# FPGA_VCC.net
KiCad netlist of a schematic drawn in Altium Designer
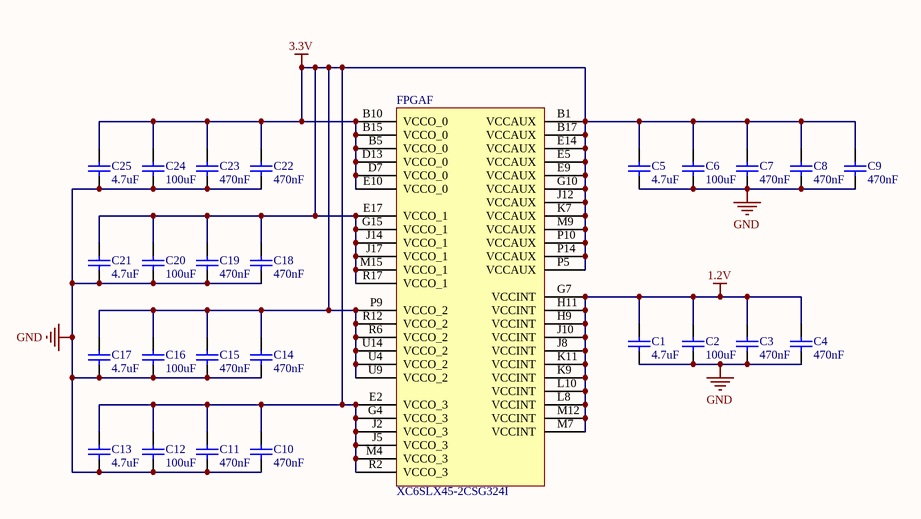
[diagram p0: FPGA_VCC.SchDoc]

(export (version "E")
  (design (tool "Eeschema 10.0.6"))
  (components
    (comp (ref "C1")
      (value "4.7uF")
      (footprint "CAPC0603(1608)100_N")
      (description "CAP 0.5pF 10V Â±0.1pF 0603 (1608 Metric) Thickness 1mm SMD")
      (fields (field (name "TOLERANCE") "Â±0.1pF"))
      (libsource (lib "Altium Inc") (part "CMP-1035-00001-1"))
    )
    (comp (ref "C2")
      (value "100uF")
      (footprint "CAPC0805(2012)75_N")
      (description "CAP 0.5pF 10V Â±0.1pF 0805 (2012 Metric) Thickness 0.75mm SMD")
      (fields (field (name "TOLERANCE") "Â±0.1pF"))
      (libsource (lib "Altium Inc") (part "CMP-1036-00001-1"))
    )
    (comp (ref "C3")
      (value "470nF")
      (footprint "CAPC0603(1608)100_N")
      (description "CAP 0.5pF 10V Â±0.1pF 0603 (1608 Metric) Thickness 1mm SMD")
      (fields (field (name "TOLERANCE") "Â±0.1pF"))
      (libsource (lib "Altium Inc") (part "CMP-1035-00001-1"))
    )
    (comp (ref "C4")
      (value "470nF")
      (footprint "CAPC0603(1608)100_N")
      (description "CAP 0.5pF 10V Â±0.1pF 0603 (1608 Metric) Thickness 1mm SMD")
      (fields (field (name "TOLERANCE") "Â±0.1pF"))
      (libsource (lib "Altium Inc") (part "CMP-1035-00001-1"))
    )
    (comp (ref "C5")
      (value "4.7uF")
      (footprint "CAPC0603(1608)100_N")
      (description "CAP 0.5pF 10V Â±0.1pF 0603 (1608 Metric) Thickness 1mm SMD")
      (fields (field (name "TOLERANCE") "Â±0.1pF"))
      (libsource (lib "Altium Inc") (part "CMP-1035-00001-1"))
    )
    (comp (ref "C6")
      (value "100uF")
      (footprint "CAPC0805(2012)75_N")
      (description "CAP 0.5pF 10V Â±0.1pF 0805 (2012 Metric) Thickness 0.75mm SMD")
      (fields (field (name "TOLERANCE") "Â±0.1pF"))
      (libsource (lib "Altium Inc") (part "CMP-1036-00001-1"))
    )
    (comp (ref "C7")
      (value "470nF")
      (footprint "CAPC0603(1608)100_N")
      (description "CAP 0.5pF 10V Â±0.1pF 0603 (1608 Metric) Thickness 1mm SMD")
      (fields (field (name "TOLERANCE") "Â±0.1pF"))
      (libsource (lib "Altium Inc") (part "CMP-1035-00001-1"))
    )
    (comp (ref "C8")
      (value "470nF")
      (footprint "CAPC0603(1608)100_N")
      (description "CAP 0.5pF 10V Â±0.1pF 0603 (1608 Metric) Thickness 1mm SMD")
      (fields (field (name "TOLERANCE") "Â±0.1pF"))
      (libsource (lib "Altium Inc") (part "CMP-1035-00001-1"))
    )
    (comp (ref "C9")
      (value "470nF")
      (footprint "CAPC0603(1608)100_N")
      (description "CAP 0.5pF 10V Â±0.1pF 0603 (1608 Metric) Thickness 1mm SMD")
      (fields (field (name "TOLERANCE") "Â±0.1pF"))
      (libsource (lib "Altium Inc") (part "CMP-1035-00001-1"))
    )
    (comp (ref "C10")
      (value "470nF")
      (footprint "CAPC0603(1608)100_N")
      (description "CAP 0.5pF 10V Â±0.1pF 0603 (1608 Metric) Thickness 1mm SMD")
      (fields (field (name "TOLERANCE") "Â±0.1pF"))
      (libsource (lib "Altium Inc") (part "CMP-1035-00001-1"))
    )
    (comp (ref "C11")
      (value "470nF")
      (footprint "CAPC0603(1608)100_N")
      (description "CAP 0.5pF 10V Â±0.1pF 0603 (1608 Metric) Thickness 1mm SMD")
      (fields (field (name "TOLERANCE") "Â±0.1pF"))
      (libsource (lib "Altium Inc") (part "CMP-1035-00001-1"))
    )
    (comp (ref "C12")
      (value "100uF")
      (footprint "CAPC0805(2012)75_N")
      (description "CAP 0.5pF 10V Â±0.1pF 0805 (2012 Metric) Thickness 0.75mm SMD")
      (fields (field (name "TOLERANCE") "Â±0.1pF"))
      (libsource (lib "Altium Inc") (part "CMP-1036-00001-1"))
    )
    (comp (ref "C13")
      (value "4.7uF")
      (footprint "CAPC0603(1608)100_N")
      (description "CAP 0.5pF 10V Â±0.1pF 0603 (1608 Metric) Thickness 1mm SMD")
      (fields (field (name "TOLERANCE") "Â±0.1pF"))
      (libsource (lib "Altium Inc") (part "CMP-1035-00001-1"))
    )
    (comp (ref "C14")
      (value "470nF")
      (footprint "CAPC0603(1608)100_N")
      (description "CAP 0.5pF 10V Â±0.1pF 0603 (1608 Metric) Thickness 1mm SMD")
      (fields (field (name "TOLERANCE") "Â±0.1pF"))
      (libsource (lib "Altium Inc") (part "CMP-1035-00001-1"))
    )
    (comp (ref "C15")
      (value "470nF")
      (footprint "CAPC0603(1608)100_N")
      (description "CAP 0.5pF 10V Â±0.1pF 0603 (1608 Metric) Thickness 1mm SMD")
      (fields (field (name "TOLERANCE") "Â±0.1pF"))
      (libsource (lib "Altium Inc") (part "CMP-1035-00001-1"))
    )
    (comp (ref "C16")
      (value "100uF")
      (footprint "CAPC0805(2012)75_N")
      (description "CAP 0.5pF 10V Â±0.1pF 0805 (2012 Metric) Thickness 0.75mm SMD")
      (fields (field (name "TOLERANCE") "Â±0.1pF"))
      (libsource (lib "Altium Inc") (part "CMP-1036-00001-1"))
    )
    (comp (ref "C17")
      (value "4.7uF")
      (footprint "CAPC0603(1608)100_N")
      (description "CAP 0.5pF 10V Â±0.1pF 0603 (1608 Metric) Thickness 1mm SMD")
      (fields (field (name "TOLERANCE") "Â±0.1pF"))
      (libsource (lib "Altium Inc") (part "CMP-1035-00001-1"))
    )
    (comp (ref "C18")
      (value "470nF")
      (footprint "CAPC0603(1608)100_N")
      (description "CAP 0.5pF 10V Â±0.1pF 0603 (1608 Metric) Thickness 1mm SMD")
      (fields (field (name "TOLERANCE") "Â±0.1pF"))
      (libsource (lib "Altium Inc") (part "CMP-1035-00001-1"))
    )
    (comp (ref "C19")
      (value "470nF")
      (footprint "CAPC0603(1608)100_N")
      (description "CAP 0.5pF 10V Â±0.1pF 0603 (1608 Metric) Thickness 1mm SMD")
      (fields (field (name "TOLERANCE") "Â±0.1pF"))
      (libsource (lib "Altium Inc") (part "CMP-1035-00001-1"))
    )
    (comp (ref "C20")
      (value "100uF")
      (footprint "CAPC0805(2012)75_N")
      (description "CAP 0.5pF 10V Â±0.1pF 0805 (2012 Metric) Thickness 0.75mm SMD")
      (fields (field (name "TOLERANCE") "Â±0.1pF"))
      (libsource (lib "Altium Inc") (part "CMP-1036-00001-1"))
    )
    (comp (ref "C21")
      (value "4.7uF")
      (footprint "CAPC0603(1608)100_N")
      (description "CAP 0.5pF 10V Â±0.1pF 0603 (1608 Metric) Thickness 1mm SMD")
      (fields (field (name "TOLERANCE") "Â±0.1pF"))
      (libsource (lib "Altium Inc") (part "CMP-1035-00001-1"))
    )
    (comp (ref "C22")
      (value "470nF")
      (footprint "CAPC0603(1608)100_N")
      (description "CAP 0.5pF 10V Â±0.1pF 0603 (1608 Metric) Thickness 1mm SMD")
      (fields (field (name "TOLERANCE") "Â±0.1pF"))
      (libsource (lib "Altium Inc") (part "CMP-1035-00001-1"))
    )
    (comp (ref "C23")
      (value "470nF")
      (footprint "CAPC0603(1608)100_N")
      (description "CAP 0.5pF 10V Â±0.1pF 0603 (1608 Metric) Thickness 1mm SMD")
      (fields (field (name "TOLERANCE") "Â±0.1pF"))
      (libsource (lib "Altium Inc") (part "CMP-1035-00001-1"))
    )
    (comp (ref "C24")
      (value "100uF")
      (footprint "CAPC0805(2012)75_N")
      (description "CAP 0.5pF 10V Â±0.1pF 0805 (2012 Metric) Thickness 0.75mm SMD")
      (fields (field (name "TOLERANCE") "Â±0.1pF"))
      (libsource (lib "Altium Inc") (part "CMP-1036-00001-1"))
    )
    (comp (ref "C25")
      (value "4.7uF")
      (footprint "CAPC0603(1608)100_N")
      (description "CAP 0.5pF 10V Â±0.1pF 0603 (1608 Metric) Thickness 1mm SMD")
      (fields (field (name "TOLERANCE") "Â±0.1pF"))
      (libsource (lib "Altium Inc") (part "CMP-1035-00001-1"))
    )
    (comp (ref "FPGA")
      (value "XC6SLX45-2CSG324I")
      (footprint "CSG324")
      (libsource (lib "Xilinx Spartan-6") (part "XC6SLX45-2CSG324I"))
    )
  )
  (nets
    (net (code "1") (name "1.2V") (class "Default")
      (node (ref "C1") (pin "2") (pinfunction "2_2") (pintype "passive"))
      (node (ref "C2") (pin "2") (pinfunction "2_2") (pintype "passive"))
      (node (ref "C3") (pin "2") (pinfunction "2_2") (pintype "passive"))
      (node (ref "C4") (pin "2") (pinfunction "2_2") (pintype "passive"))
      (node (ref "FPGA") (pin "G7") (pinfunction "VCCINT_G7") (pintype "power_in"))
      (node (ref "FPGA") (pin "H11") (pinfunction "VCCINT_H11") (pintype "power_in"))
      (node (ref "FPGA") (pin "H9") (pinfunction "VCCINT_H9") (pintype "power_in"))
      (node (ref "FPGA") (pin "J10") (pinfunction "VCCINT_J10") (pintype "power_in"))
      (node (ref "FPGA") (pin "J8") (pinfunction "VCCINT_J8") (pintype "power_in"))
      (node (ref "FPGA") (pin "K11") (pinfunction "VCCINT_K11") (pintype "power_in"))
      (node (ref "FPGA") (pin "K9") (pinfunction "VCCINT_K9") (pintype "power_in"))
      (node (ref "FPGA") (pin "L10") (pinfunction "VCCINT_L10") (pintype "power_in"))
      (node (ref "FPGA") (pin "L8") (pinfunction "VCCINT_L8") (pintype "power_in"))
      (node (ref "FPGA") (pin "M12") (pinfunction "VCCINT_M12") (pintype "power_in"))
      (node (ref "FPGA") (pin "M7") (pinfunction "VCCINT_M7") (pintype "power_in"))
    )
    (net (code "2") (name "3.3V") (class "Default")
      (node (ref "C10") (pin "2") (pinfunction "2_2") (pintype "passive"))
      (node (ref "C11") (pin "2") (pinfunction "2_2") (pintype "passive"))
      (node (ref "C12") (pin "2") (pinfunction "2_2") (pintype "passive"))
      (node (ref "C13") (pin "2") (pinfunction "2_2") (pintype "passive"))
      (node (ref "C14") (pin "2") (pinfunction "2_2") (pintype "passive"))
      (node (ref "C15") (pin "2") (pinfunction "2_2") (pintype "passive"))
      (node (ref "C16") (pin "2") (pinfunction "2_2") (pintype "passive"))
      (node (ref "C17") (pin "2") (pinfunction "2_2") (pintype "passive"))
      (node (ref "C18") (pin "2") (pinfunction "2_2") (pintype "passive"))
      (node (ref "C19") (pin "2") (pinfunction "2_2") (pintype "passive"))
      (node (ref "C20") (pin "2") (pinfunction "2_2") (pintype "passive"))
      (node (ref "C21") (pin "2") (pinfunction "2_2") (pintype "passive"))
      (node (ref "C22") (pin "2") (pinfunction "2_2") (pintype "passive"))
      (node (ref "C23") (pin "2") (pinfunction "2_2") (pintype "passive"))
      (node (ref "C24") (pin "2") (pinfunction "2_2") (pintype "passive"))
      (node (ref "C25") (pin "2") (pinfunction "2_2") (pintype "passive"))
      (node (ref "C5") (pin "2") (pinfunction "2_2") (pintype "passive"))
      (node (ref "C6") (pin "2") (pinfunction "2_2") (pintype "passive"))
      (node (ref "C7") (pin "2") (pinfunction "2_2") (pintype "passive"))
      (node (ref "C8") (pin "2") (pinfunction "2_2") (pintype "passive"))
      (node (ref "C9") (pin "2") (pinfunction "2_2") (pintype "passive"))
      (node (ref "FPGA") (pin "B1") (pinfunction "VCCAUX_B1") (pintype "power_in"))
      (node (ref "FPGA") (pin "B10") (pinfunction "VCCO_0_B10") (pintype "power_in"))
      (node (ref "FPGA") (pin "B15") (pinfunction "VCCO_0_B15") (pintype "power_in"))
      (node (ref "FPGA") (pin "B17") (pinfunction "VCCAUX_B17") (pintype "power_in"))
      (node (ref "FPGA") (pin "B5") (pinfunction "VCCO_0_B5") (pintype "power_in"))
      (node (ref "FPGA") (pin "D13") (pinfunction "VCCO_0_D13") (pintype "power_in"))
      (node (ref "FPGA") (pin "D7") (pinfunction "VCCO_0_D7") (pintype "power_in"))
      (node (ref "FPGA") (pin "E10") (pinfunction "VCCO_0_E10") (pintype "power_in"))
      (node (ref "FPGA") (pin "E14") (pinfunction "VCCAUX_E14") (pintype "power_in"))
      (node (ref "FPGA") (pin "E17") (pinfunction "VCCO_1_E17") (pintype "power_in"))
      (node (ref "FPGA") (pin "E2") (pinfunction "VCCO_3_E2") (pintype "power_in"))
      (node (ref "FPGA") (pin "E5") (pinfunction "VCCAUX_E5") (pintype "power_in"))
      (node (ref "FPGA") (pin "E9") (pinfunction "VCCAUX_E9") (pintype "power_in"))
      (node (ref "FPGA") (pin "G10") (pinfunction "VCCAUX_G10") (pintype "power_in"))
      (node (ref "FPGA") (pin "G15") (pinfunction "VCCO_1_G15") (pintype "power_in"))
      (node (ref "FPGA") (pin "G4") (pinfunction "VCCO_3_G4") (pintype "power_in"))
      (node (ref "FPGA") (pin "J12") (pinfunction "VCCAUX_J12") (pintype "power_in"))
      (node (ref "FPGA") (pin "J14") (pinfunction "VCCO_1_J14") (pintype "power_in"))
      (node (ref "FPGA") (pin "J17") (pinfunction "VCCO_1_J17") (pintype "power_in"))
      (node (ref "FPGA") (pin "J2") (pinfunction "VCCO_3_J2") (pintype "power_in"))
      (node (ref "FPGA") (pin "J5") (pinfunction "VCCO_3_J5") (pintype "power_in"))
      (node (ref "FPGA") (pin "K7") (pinfunction "VCCAUX_K7") (pintype "power_in"))
      (node (ref "FPGA") (pin "M15") (pinfunction "VCCO_1_M15") (pintype "power_in"))
      (node (ref "FPGA") (pin "M4") (pinfunction "VCCO_3_M4") (pintype "power_in"))
      (node (ref "FPGA") (pin "M9") (pinfunction "VCCAUX_M9") (pintype "power_in"))
      (node (ref "FPGA") (pin "P10") (pinfunction "VCCAUX_P10") (pintype "power_in"))
      (node (ref "FPGA") (pin "P14") (pinfunction "VCCAUX_P14") (pintype "power_in"))
      (node (ref "FPGA") (pin "P5") (pinfunction "VCCAUX_P5") (pintype "power_in"))
      (node (ref "FPGA") (pin "P9") (pinfunction "VCCO_2_P9") (pintype "power_in"))
      (node (ref "FPGA") (pin "R12") (pinfunction "VCCO_2_R12") (pintype "power_in"))
      (node (ref "FPGA") (pin "R17") (pinfunction "VCCO_1_R17") (pintype "power_in"))
      (node (ref "FPGA") (pin "R2") (pinfunction "VCCO_3_R2") (pintype "power_in"))
      (node (ref "FPGA") (pin "R6") (pinfunction "VCCO_2_R6") (pintype "power_in"))
      (node (ref "FPGA") (pin "U14") (pinfunction "VCCO_2_U14") (pintype "power_in"))
      (node (ref "FPGA") (pin "U4") (pinfunction "VCCO_2_U4") (pintype "power_in"))
      (node (ref "FPGA") (pin "U9") (pinfunction "VCCO_2_U9") (pintype "power_in"))
    )
    (net (code "3") (name "GND") (class "Default")
      (node (ref "C1") (pin "1") (pinfunction "1_1") (pintype "passive"))
      (node (ref "C10") (pin "1") (pinfunction "1_1") (pintype "passive"))
      (node (ref "C11") (pin "1") (pinfunction "1_1") (pintype "passive"))
      (node (ref "C12") (pin "1") (pinfunction "1_1") (pintype "passive"))
      (node (ref "C13") (pin "1") (pinfunction "1_1") (pintype "passive"))
      (node (ref "C14") (pin "1") (pinfunction "1_1") (pintype "passive"))
      (node (ref "C15") (pin "1") (pinfunction "1_1") (pintype "passive"))
      (node (ref "C16") (pin "1") (pinfunction "1_1") (pintype "passive"))
      (node (ref "C17") (pin "1") (pinfunction "1_1") (pintype "passive"))
      (node (ref "C18") (pin "1") (pinfunction "1_1") (pintype "passive"))
      (node (ref "C19") (pin "1") (pinfunction "1_1") (pintype "passive"))
      (node (ref "C2") (pin "1") (pinfunction "1_1") (pintype "passive"))
      (node (ref "C20") (pin "1") (pinfunction "1_1") (pintype "passive"))
      (node (ref "C21") (pin "1") (pinfunction "1_1") (pintype "passive"))
      (node (ref "C22") (pin "1") (pinfunction "1_1") (pintype "passive"))
      (node (ref "C23") (pin "1") (pinfunction "1_1") (pintype "passive"))
      (node (ref "C24") (pin "1") (pinfunction "1_1") (pintype "passive"))
      (node (ref "C25") (pin "1") (pinfunction "1_1") (pintype "passive"))
      (node (ref "C3") (pin "1") (pinfunction "1_1") (pintype "passive"))
      (node (ref "C4") (pin "1") (pinfunction "1_1") (pintype "passive"))
      (node (ref "C5") (pin "1") (pinfunction "1_1") (pintype "passive"))
      (node (ref "C6") (pin "1") (pinfunction "1_1") (pintype "passive"))
      (node (ref "C7") (pin "1") (pinfunction "1_1") (pintype "passive"))
      (node (ref "C8") (pin "1") (pinfunction "1_1") (pintype "passive"))
      (node (ref "C9") (pin "1") (pinfunction "1_1") (pintype "passive"))
    )
  )
)
